# Motor-Driver.net
KiCad netlist of a schematic drawn in EAGLE
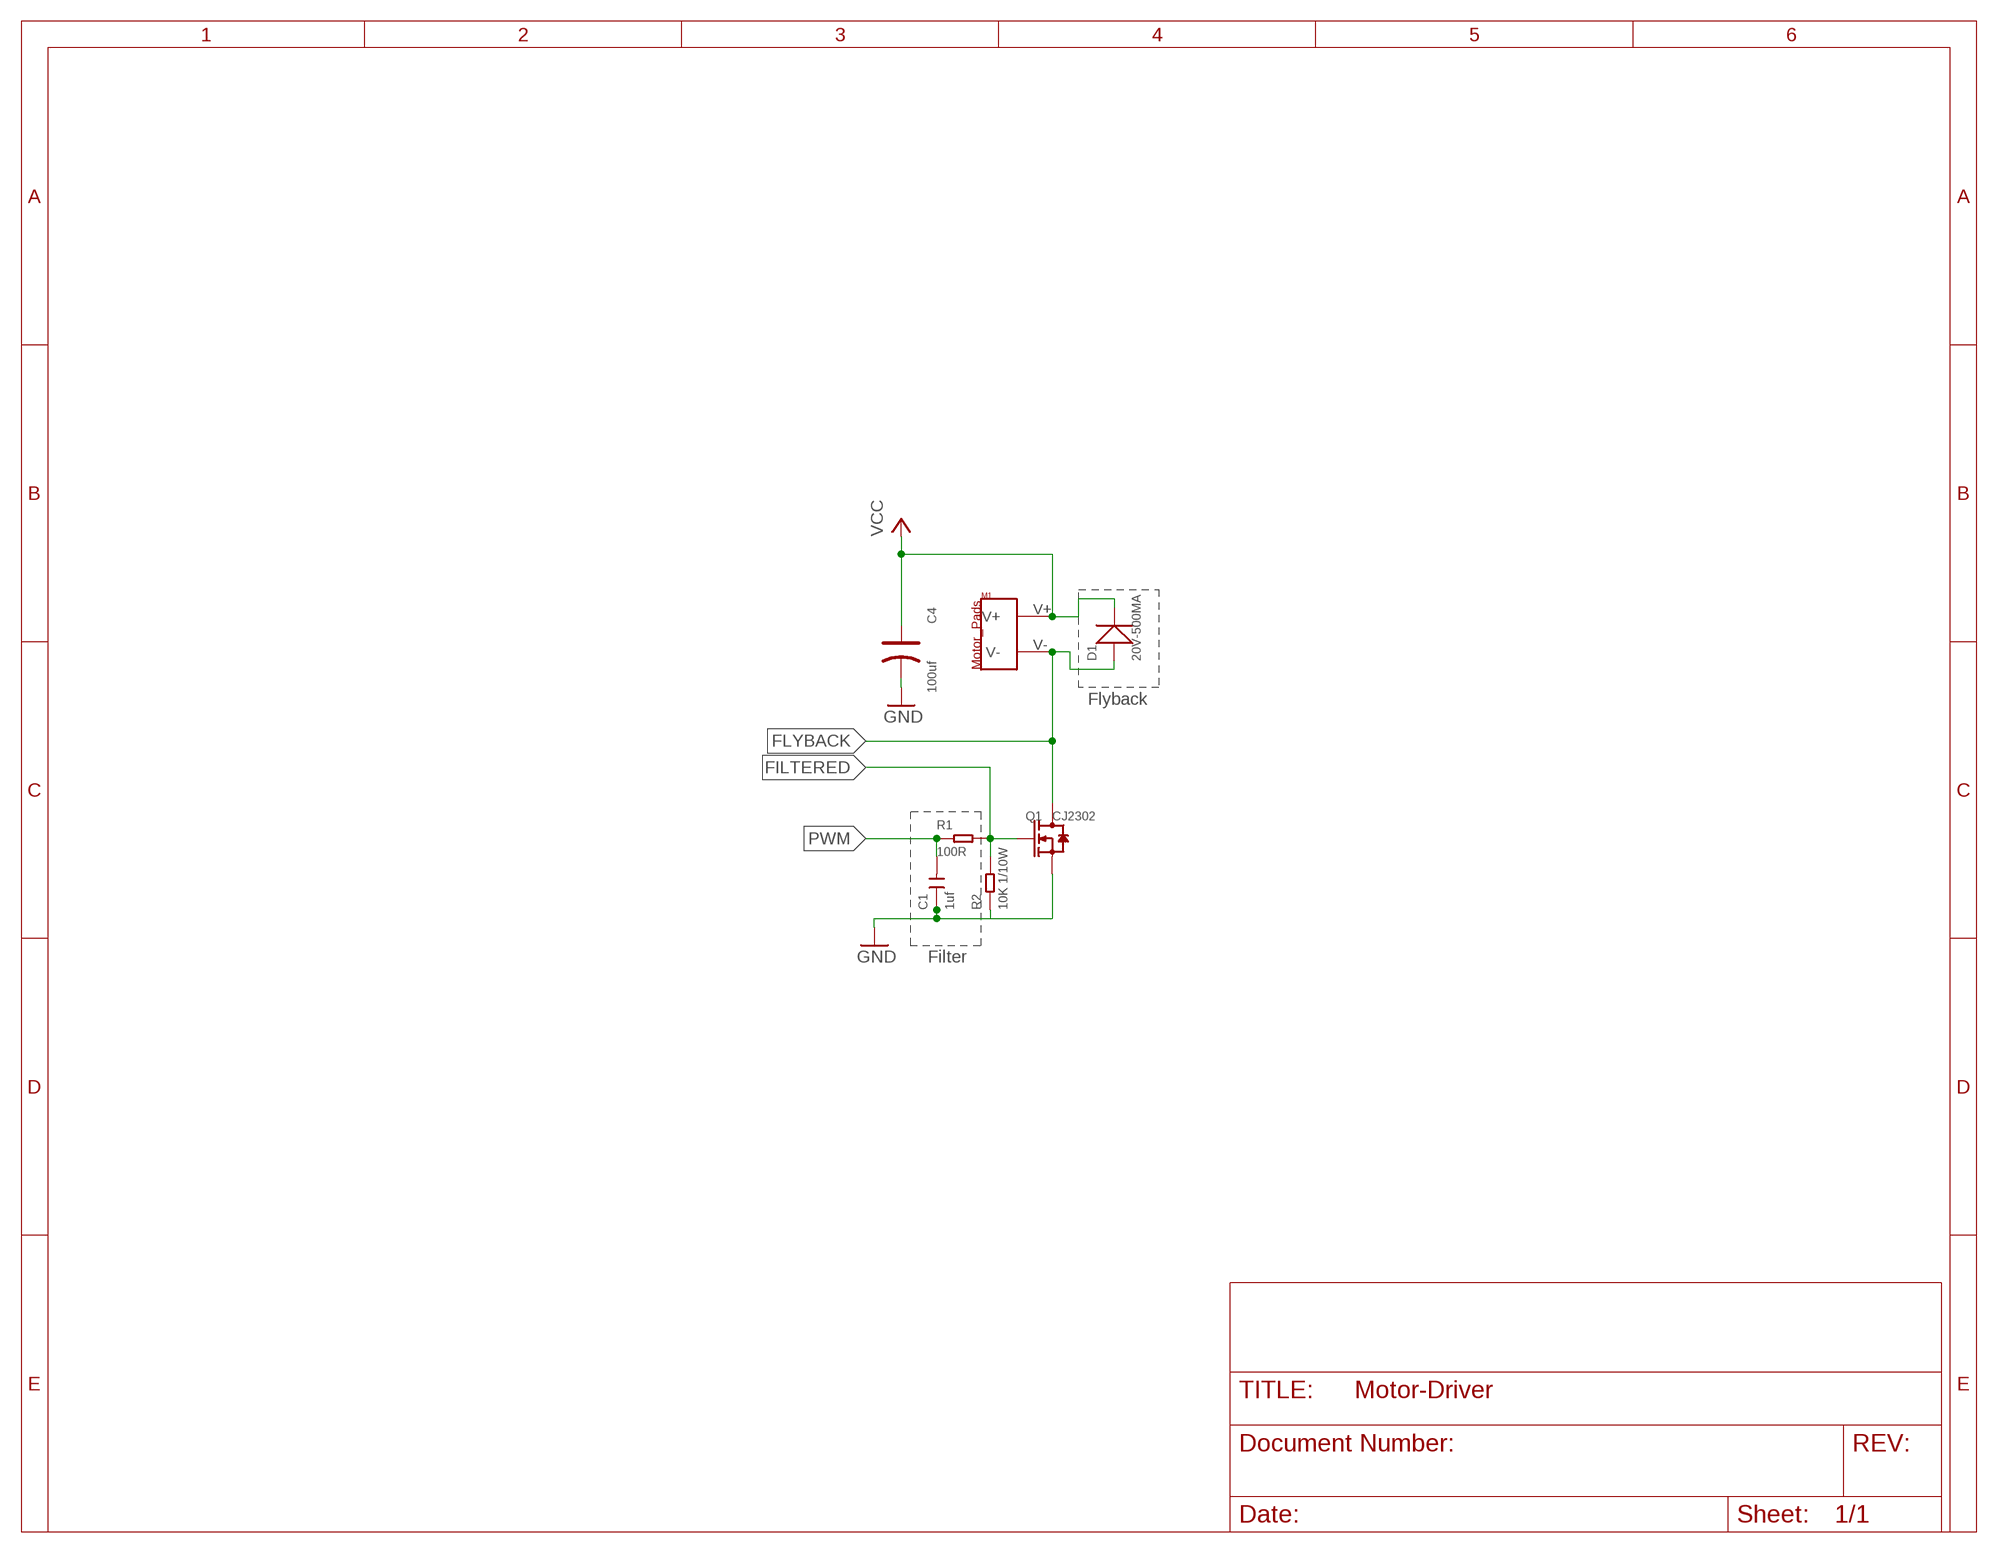
[diagram p0: schematic, sheet 1]

(export (version "E")
  (design (tool "Eeschema 10.0.6"))
  (components
    (comp (ref "C1")
      (value "1uf")
      (footprint "eagle-import:C0402")
      (fields (field (name "MPN") "CC0402KRX5R6BB105"))
      (libsource (lib "eagle-import") (part "CERAMIC-1UF-10V-10%-X5R(0402)"))
    )
    (comp (ref "C4")
      (value "100uf")
      (footprint "eagle-import:AVX-B")
      (fields (field (name "MPN") "TAJB107M010#NJ"))
      (libsource (lib "eagle-import") (part "TANTALUM-SMD-100UF-10V(AVX-B)"))
    )
    (comp (ref "D1")
      (value "20V-500MA")
      (footprint "eagle-import:SOD-123")
      (fields (field (name "MPN") "SS0520-7-F"))
      (libsource (lib "eagle-import") (part "SMD-DIODE-SCHOTTKY-20V-500MA(SOD-123)"))
    )
    (comp (ref "M1")
      (value "MOTOR_PADS")
      (footprint "eagle-import:MOTOR_PADS")
      (libsource (lib "eagle-import") (part "MOTOR_PADS"))
    )
    (comp (ref "Q1")
      (value "CJ2302")
      (footprint "eagle-import:SOT-23")
      (libsource (lib "eagle-import") (part "SMD-MOSFET-N-CH-20V-2.1A-CJ2302(SOT-23)"))
    )
    (comp (ref "R1")
      (value "100R")
      (footprint "eagle-import:R0603")
      (fields (field (name "MPN") "RC0603JR-07100RL"))
      (libsource (lib "eagle-import") (part "SMD-RES-100R-5%-1/10W(0603)"))
    )
    (comp (ref "R2")
      (value "10K 1/10W")
      (footprint "eagle-import:R0603")
      (fields (field (name "MPN") "RC0603JR-0710KL"))
      (libsource (lib "eagle-import") (part "SMD-RES-10K-5%-1/10W(0603)"))
    )
  )
  (nets
    (net (code "1") (name "FILTERED") (class "Default")
      (node (ref "Q1") (pin "1") (pinfunction "G_1") (pintype "passive"))
      (node (ref "R1") (pin "2") (pinfunction "2_2") (pintype "passive"))
      (node (ref "R2") (pin "2") (pinfunction "2_2") (pintype "passive"))
    )
    (net (code "2") (name "FLYBACK") (class "Default")
      (node (ref "D1") (pin "+") (pinfunction "+_+") (pintype "passive"))
      (node (ref "M1") (pin "V-") (pinfunction "V-_V-") (pintype "bidirectional"))
      (node (ref "Q1") (pin "3") (pinfunction "D_3") (pintype "passive"))
    )
    (net (code "3") (name "GND") (class "Default")
      (node (ref "C1") (pin "1") (pinfunction "1_1") (pintype "passive"))
      (node (ref "C4") (pin "-") (pinfunction "-_-") (pintype "passive"))
      (node (ref "Q1") (pin "2") (pinfunction "S_2") (pintype "passive"))
      (node (ref "R2") (pin "1") (pinfunction "1_1") (pintype "passive"))
    )
    (net (code "4") (name "PWM") (class "Default")
      (node (ref "C1") (pin "2") (pinfunction "2_2") (pintype "passive"))
      (node (ref "R1") (pin "1") (pinfunction "1_1") (pintype "passive"))
    )
    (net (code "5") (name "VCC") (class "Default")
      (node (ref "C4") (pin "+") (pinfunction "+_+") (pintype "passive"))
      (node (ref "D1") (pin "-") (pinfunction "-_-") (pintype "passive"))
      (node (ref "M1") (pin "V+") (pinfunction "V+_V+") (pintype "bidirectional"))
    )
  )
)
